# Schematic.net
KiCad netlist of a schematic drawn in Altium Designer
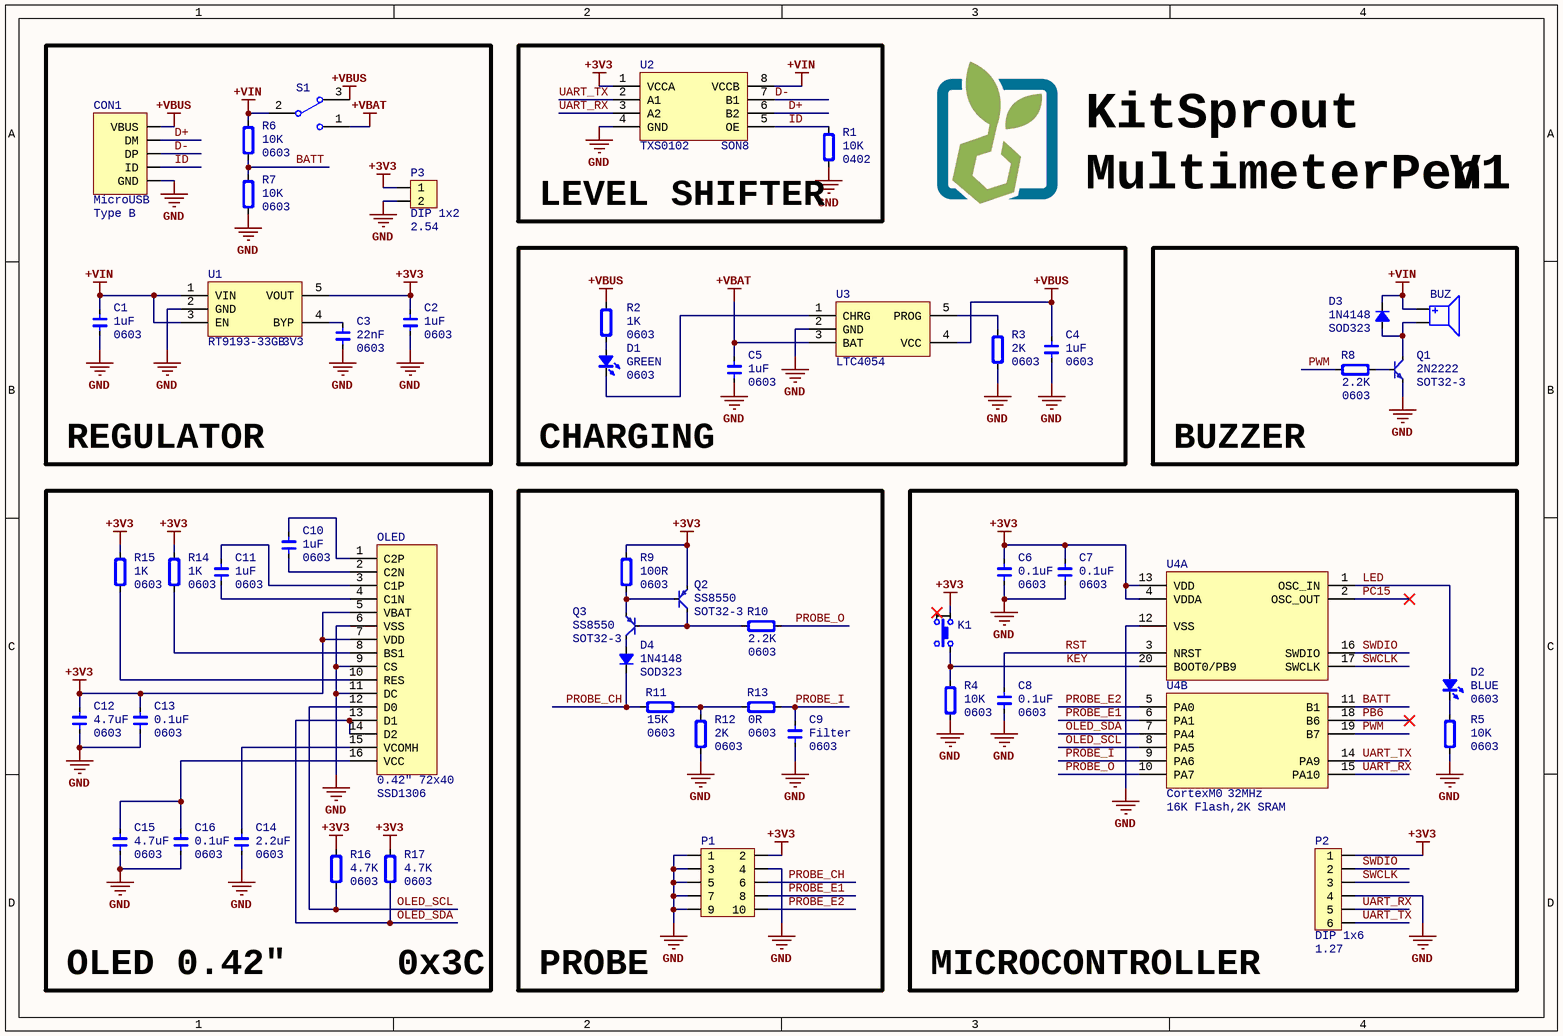
[diagram p0: Schematic.SchDoc]

(export (version "E")
  (design (tool "Eeschema 10.0.6"))
  (components
    (comp (ref "BUZ")
      (value "Buzzer")
      (footprint "PCB_Module:Buzzer_5x5")
      (libsource (lib "SCH_Module") (part "Buzzer"))
    )
    (comp (ref "C1")
      (value "1uF")
      (footprint "PCB_PassiveCap:CAP_0603")
      (description "Capacitor")
      (fields (field (name "TYPE") "0603") (field (name "Comment") "C0603"))
      (libsource (lib "SCH_Passive") (part "Cap_0603"))
    )
    (comp (ref "C2")
      (value "1uF")
      (footprint "PCB_PassiveCap:CAP_0603")
      (description "Capacitor")
      (fields (field (name "TYPE") "0603") (field (name "Comment") "C0603"))
      (libsource (lib "SCH_Passive") (part "Cap_0603"))
    )
    (comp (ref "C3")
      (value "22nF")
      (footprint "PCB_PassiveCap:CAP_0603")
      (description "Capacitor")
      (fields (field (name "TYPE") "0603") (field (name "Comment") "C0603"))
      (libsource (lib "SCH_Passive") (part "Cap_0603"))
    )
    (comp (ref "C4")
      (value "1uF")
      (footprint "PCB_PassiveCap:CAP_0603")
      (description "Capacitor")
      (fields (field (name "TYPE") "0603") (field (name "Comment") "C0603"))
      (libsource (lib "SCH_Passive") (part "Cap_0603"))
    )
    (comp (ref "C5")
      (value "1uF")
      (footprint "PCB_PassiveCap:CAP_0603")
      (description "Capacitor")
      (fields (field (name "TYPE") "0603") (field (name "Comment") "C0603"))
      (libsource (lib "SCH_Passive") (part "Cap_0603"))
    )
    (comp (ref "C6")
      (value "0.1uF")
      (footprint "PCB_PassiveCap:CAP_0603")
      (description "Capacitor")
      (fields (field (name "TYPE") "0603") (field (name "Comment") "C0603"))
      (libsource (lib "SCH_Passive") (part "Cap_0603"))
    )
    (comp (ref "C7")
      (value "0.1uF")
      (footprint "PCB_PassiveCap:CAP_0603")
      (description "Capacitor")
      (fields (field (name "TYPE") "0603") (field (name "Comment") "C0603"))
      (libsource (lib "SCH_Passive") (part "Cap_0603"))
    )
    (comp (ref "C8")
      (value "0.1uF")
      (footprint "PCB_PassiveCap:CAP_0603")
      (description "Capacitor")
      (fields (field (name "TYPE") "0603") (field (name "Comment") "C0603"))
      (libsource (lib "SCH_Passive") (part "Cap_0603"))
    )
    (comp (ref "C9")
      (value "Filter")
      (footprint "PCB_PassiveCap:CAP_0603")
      (description "Capacitor")
      (fields (field (name "TYPE") "0603") (field (name "Comment") "C0603"))
      (libsource (lib "SCH_Passive") (part "Cap_0603"))
    )
    (comp (ref "C10")
      (value "1uF")
      (footprint "PCB_PassiveCap:CAP_0603")
      (description "Capacitor")
      (fields (field (name "TYPE") "0603") (field (name "Comment") "C0603"))
      (libsource (lib "SCH_Passive") (part "Cap_0603"))
    )
    (comp (ref "C11")
      (value "1uF")
      (footprint "PCB_PassiveCap:CAP_0603")
      (description "Capacitor")
      (fields (field (name "TYPE") "0603") (field (name "Comment") "C0603"))
      (libsource (lib "SCH_Passive") (part "Cap_0603"))
    )
    (comp (ref "C12")
      (value "4.7uF")
      (footprint "PCB_PassiveCap:CAP_0603")
      (description "Capacitor")
      (fields (field (name "TYPE") "0603") (field (name "Comment") "C0603"))
      (libsource (lib "SCH_Passive") (part "Cap_0603"))
    )
    (comp (ref "C13")
      (value "0.1uF")
      (footprint "PCB_PassiveCap:CAP_0603")
      (description "Capacitor")
      (fields (field (name "TYPE") "0603") (field (name "Comment") "C0603"))
      (libsource (lib "SCH_Passive") (part "Cap_0603"))
    )
    (comp (ref "C14")
      (value "2.2uF")
      (footprint "PCB_PassiveCap:CAP_0603")
      (description "Capacitor")
      (fields (field (name "TYPE") "0603") (field (name "Comment") "C0603"))
      (libsource (lib "SCH_Passive") (part "Cap_0603"))
    )
    (comp (ref "C15")
      (value "4.7uF")
      (footprint "PCB_PassiveCap:CAP_0603")
      (description "Capacitor")
      (fields (field (name "TYPE") "0603") (field (name "Comment") "C0603"))
      (libsource (lib "SCH_Passive") (part "Cap_0603"))
    )
    (comp (ref "C16")
      (value "0.1uF")
      (footprint "PCB_PassiveCap:CAP_0603")
      (description "Capacitor")
      (fields (field (name "TYPE") "0603") (field (name "Comment") "C0603"))
      (libsource (lib "SCH_Passive") (part "Cap_0603"))
    )
    (comp (ref "CON1")
      (value "MicroUSB")
      (footprint "PCB_USB:USB_Micro-AB")
      (description "USB")
      (fields (field (name "ALTIUM_VALUE") "Type B"))
      (libsource (lib "SCH_USB") (part "USB_Micro"))
    )
    (comp (ref "D1")
      (value "GREEN")
      (footprint "PCB_ActiveLED:LED_0603_GREEN")
      (description "LED")
      (fields (field (name "TYPE") "0603") (field (name "Comment") "D0603"))
      (libsource (lib "SCH_Active") (part "LED_0603"))
    )
    (comp (ref "D2")
      (value "BLUE")
      (footprint "PCB_ActiveLED:LED_0603_BLUE")
      (description "LED")
      (fields (field (name "TYPE") "0603") (field (name "Comment") "D0603"))
      (libsource (lib "SCH_Active") (part "LED_0603"))
    )
    (comp (ref "D3")
      (value "1N4148")
      (footprint "PCB_ActiveDIO:SOD-323")
      (description "Diode")
      (fields (field (name "TYPE") "SOD323"))
      (libsource (lib "SCH_Active") (part "Diode_SOD323"))
    )
    (comp (ref "D4")
      (value "1N4148")
      (footprint "PCB_ActiveDIO:SOD-323")
      (description "Diode")
      (fields (field (name "TYPE") "SOD323"))
      (libsource (lib "SCH_Active") (part "Diode_SOD323"))
    )
    (comp (ref "K1")
      (value "TACT")
      (footprint "PCB_Switch:ButtonTACT_3.4*3.5_90")
      (description "Button")
      (libsource (lib "SCH_Switch") (part "ButtonTACT_90_3.4x3.5"))
    )
    (comp (ref "OLED")
      (value "0.42\" 72x40")
      (footprint "PCB_Module:OLED_0.42_72x40_SSD1306")
      (description "OLED")
      (fields (field (name "NOTE") "SSD1306") (field (name "Comment") "OLED_0.42_SSD1306"))
      (libsource (lib "SCH_Module") (part "OLED_0.42_SSD1306"))
    )
    (comp (ref "P1")
      (value "HDR2x5")
      (footprint "PCB_ConnectorHDR:HDR2X5_2.54_180HF")
      (description "Header")
      (libsource (lib "SCH_ConnectorHDR") (part "HDR2x5_2.54"))
    )
    (comp (ref "P2")
      (value "1.27")
      (footprint "PCB_ConnectorHDR:HDR1X6_1.27_180F")
      (description "Header")
      (fields (field (name "TYPE") "DIP 1x6") (field (name "Comment") "HDR1x6"))
      (libsource (lib "SCH_ConnectorHDR") (part "HDR1x6_1.27T"))
    )
    (comp (ref "P3")
      (value "2.54")
      (footprint "PCB_ConnectorHDR:HDR1X2_2.54_180H")
      (description "Header")
      (fields (field (name "TYPE") "DIP 1x2") (field (name "Comment") "HDR1x2"))
      (libsource (lib "SCH_ConnectorHDR") (part "HDR1x2_2.54"))
    )
    (comp (ref "Q1")
      (value "2N2222")
      (footprint "PCB_IntegratedCircuit:SOT23-3")
      (description "Transistor")
      (fields (field (name "TYPE") "SOT32-3"))
      (libsource (lib "SCH_Active") (part "BJT_NPN"))
    )
    (comp (ref "Q2")
      (value "SS8550")
      (footprint "PCB_IntegratedCircuit:SOT23-3")
      (description "Transistor")
      (fields (field (name "TYPE") "SOT32-3"))
      (libsource (lib "SCH_Active") (part "BJT_PNP"))
    )
    (comp (ref "Q3")
      (value "SS8550")
      (footprint "PCB_IntegratedCircuit:SOT23-3")
      (description "Transistor")
      (fields (field (name "TYPE") "SOT32-3"))
      (libsource (lib "SCH_Active") (part "BJT_PNP_T"))
    )
    (comp (ref "R1")
      (value "10K")
      (footprint "PCB_PassiveRes:RES_0402")
      (description "Resistor")
      (fields (field (name "TYPE") "0402") (field (name "Comment") "R0402"))
      (libsource (lib "SCH_Passive") (part "Res_0402"))
    )
    (comp (ref "R2")
      (value "1K")
      (footprint "PCB_PassiveRes:RES_0603")
      (description "Resistor")
      (fields (field (name "TYPE") "0603") (field (name "Comment") "R0603"))
      (libsource (lib "SCH_Passive") (part "Res_0603"))
    )
    (comp (ref "R3")
      (value "2K")
      (footprint "PCB_PassiveRes:RES_0603")
      (description "Resistor")
      (fields (field (name "TYPE") "0603") (field (name "Comment") "R0603"))
      (libsource (lib "SCH_Passive") (part "Res_0603"))
    )
    (comp (ref "R4")
      (value "10K")
      (footprint "PCB_PassiveRes:RES_0603")
      (description "Resistor")
      (fields (field (name "TYPE") "0603") (field (name "Comment") "R0603"))
      (libsource (lib "SCH_Passive") (part "Res_0603"))
    )
    (comp (ref "R5")
      (value "10K")
      (footprint "PCB_PassiveRes:RES_0603")
      (description "Resistor")
      (fields (field (name "TYPE") "0603") (field (name "Comment") "R0603"))
      (libsource (lib "SCH_Passive") (part "Res_0603"))
    )
    (comp (ref "R6")
      (value "10K")
      (footprint "PCB_PassiveRes:RES_0603")
      (description "Resistor")
      (fields (field (name "TYPE") "0603") (field (name "Comment") "R0603"))
      (libsource (lib "SCH_Passive") (part "Res_0603"))
    )
    (comp (ref "R7")
      (value "10K")
      (footprint "PCB_PassiveRes:RES_0603")
      (description "Resistor")
      (fields (field (name "TYPE") "0603") (field (name "Comment") "R0603"))
      (libsource (lib "SCH_Passive") (part "Res_0603"))
    )
    (comp (ref "R8")
      (value "2.2K")
      (footprint "PCB_PassiveRes:RES_0603")
      (description "Resistor")
      (fields (field (name "TYPE") "0603") (field (name "Comment") "R0603"))
      (libsource (lib "SCH_Passive") (part "Res_0603"))
    )
    (comp (ref "R9")
      (value "100R")
      (footprint "PCB_PassiveRes:RES_0603")
      (description "Resistor")
      (fields (field (name "TYPE") "0603") (field (name "Comment") "R0603"))
      (libsource (lib "SCH_Passive") (part "Res_0603"))
    )
    (comp (ref "R10")
      (value "2.2K")
      (footprint "PCB_PassiveRes:RES_0603")
      (description "Resistor")
      (fields (field (name "TYPE") "0603") (field (name "Comment") "R0603"))
      (libsource (lib "SCH_Passive") (part "Res_0603"))
    )
    (comp (ref "R11")
      (value "15K")
      (footprint "PCB_PassiveRes:RES_0603")
      (description "Resistor")
      (fields (field (name "TYPE") "0603") (field (name "Comment") "R0603"))
      (libsource (lib "SCH_Passive") (part "Res_0603"))
    )
    (comp (ref "R12")
      (value "2K")
      (footprint "PCB_PassiveRes:RES_0603")
      (description "Resistor")
      (fields (field (name "TYPE") "0603") (field (name "Comment") "R0603"))
      (libsource (lib "SCH_Passive") (part "Res_0603"))
    )
    (comp (ref "R13")
      (value "0R")
      (footprint "PCB_PassiveRes:RES_0603")
      (description "Resistor")
      (fields (field (name "TYPE") "0603") (field (name "Comment") "R0603"))
      (libsource (lib "SCH_Passive") (part "Res_0603"))
    )
    (comp (ref "R14")
      (value "1K")
      (footprint "PCB_PassiveRes:RES_0603")
      (description "Resistor")
      (fields (field (name "TYPE") "0603") (field (name "Comment") "R0603"))
      (libsource (lib "SCH_Passive") (part "Res_0603"))
    )
    (comp (ref "R15")
      (value "1K")
      (footprint "PCB_PassiveRes:RES_0603")
      (description "Resistor")
      (fields (field (name "TYPE") "0603") (field (name "Comment") "R0603"))
      (libsource (lib "SCH_Passive") (part "Res_0603"))
    )
    (comp (ref "R16")
      (value "4.7K")
      (footprint "PCB_PassiveRes:RES_0603")
      (description "Resistor")
      (fields (field (name "TYPE") "0603") (field (name "Comment") "R0603"))
      (libsource (lib "SCH_Passive") (part "Res_0603"))
    )
    (comp (ref "R17")
      (value "4.7K")
      (footprint "PCB_PassiveRes:RES_0603")
      (description "Resistor")
      (fields (field (name "TYPE") "0603") (field (name "Comment") "R0603"))
      (libsource (lib "SCH_Passive") (part "Res_0603"))
    )
    (comp (ref "S1")
      (value "SPDT")
      (footprint "PCB_Switch:SwitchSPDT_2.8X6.6_90")
      (description "Switch")
      (libsource (lib "SCH_Switch") (part "SwitchSPDT_90_2.8x6.6"))
    )
    (comp (ref "U1")
      (value "RT9193-33GB")
      (footprint "PCB_IntegratedCircuit:SOT23-5")
      (description "Power")
      (fields (field (name "ALTIUM_VALUE") "3V3"))
      (libsource (lib "SCH_Power") (part "RT9193"))
    )
    (comp (ref "U2")
      (value "TXS0102")
      (footprint "PCB_IntegratedCircuit:SON_P0.35_8")
      (description "Level Shifter")
      (fields (field (name "TYPE") "SON8") (field (name "MANUFACTURER") "Texas Instruments"))
      (libsource (lib "SCH_IntegratedCircuit") (part "TXS0102"))
    )
    (comp (ref "U3")
      (value "LTC4054")
      (footprint "PCB_IntegratedCircuit:SOT23-5")
      (description "Battery Charger")
      (libsource (lib "SCH_Power") (part "LTC4054"))
    )
    (comp (ref "U4")
      (value "STM32L011F4U6")
      (footprint "PCB_IntegratedCircuit:QFN_P0.5_20")
      (description "MCU ST")
      (fields
        (field (name "MANUFACTURER") "STMicroelectronics")
        (field (name "NOTE") "CortexM0")
        (field (name "SPECIFICATION") "16K Flash,2K SRAM")
        (field (name "Comment") "STM32L011F4U6")
      )
      (libsource (lib "SCH_Microcontroller") (part "STM32L011F"))
    )
  )
  (nets
    (net (code "1") (name "+3V3") (class "Default")
      (node (ref "C12") (pin "2") (pinfunction "2_2") (pintype "passive"))
      (node (ref "C13") (pin "2") (pinfunction "2_2") (pintype "passive"))
      (node (ref "C2") (pin "2") (pinfunction "2_2") (pintype "passive"))
      (node (ref "C6") (pin "2") (pinfunction "2_2") (pintype "passive"))
      (node (ref "C7") (pin "2") (pinfunction "2_2") (pintype "passive"))
      (node (ref "K1") (pin "1") (pinfunction "1_1") (pintype "passive"))
      (node (ref "OLED") (pin "5") (pinfunction "VBAT_5") (pintype "passive"))
      (node (ref "OLED") (pin "7") (pinfunction "VDD_7") (pintype "passive"))
      (node (ref "P1") (pin "2") (pinfunction "2_2") (pintype "passive"))
      (node (ref "P2") (pin "1") (pinfunction "1_1") (pintype "passive"))
      (node (ref "P3") (pin "1") (pinfunction "1_1") (pintype "passive"))
      (node (ref "Q2") (pin "2") (pinfunction "E_2") (pintype "passive"))
      (node (ref "R14") (pin "2") (pinfunction "2_2") (pintype "passive"))
      (node (ref "R15") (pin "2") (pinfunction "2_2") (pintype "passive"))
      (node (ref "R16") (pin "2") (pinfunction "2_2") (pintype "passive"))
      (node (ref "R17") (pin "2") (pinfunction "2_2") (pintype "passive"))
      (node (ref "R9") (pin "2") (pinfunction "2_2") (pintype "passive"))
      (node (ref "U1") (pin "5") (pinfunction "VOUT_5") (pintype "passive"))
      (node (ref "U2") (pin "1") (pinfunction "VCCA_1") (pintype "passive"))
      (node (ref "U4") (pin "13") (pinfunction "VDD_13") (pintype "passive"))
      (node (ref "U4") (pin "4") (pinfunction "VDDA_4") (pintype "passive"))
    )
    (net (code "2") (name "+VBAT") (class "Default")
      (node (ref "C5") (pin "2") (pinfunction "2_2") (pintype "passive"))
      (node (ref "S1") (pin "1") (pinfunction "1_1") (pintype "passive"))
      (node (ref "U3") (pin "3") (pinfunction "BAT_3") (pintype "passive"))
    )
    (net (code "3") (name "+VBUS") (class "Default")
      (node (ref "C4") (pin "2") (pinfunction "2_2") (pintype "passive"))
      (node (ref "CON1") (pin "1") (pinfunction "VBUS_1") (pintype "passive"))
      (node (ref "R2") (pin "2") (pinfunction "2_2") (pintype "passive"))
      (node (ref "S1") (pin "3") (pinfunction "3_3") (pintype "passive"))
      (node (ref "U3") (pin "4") (pinfunction "VCC_4") (pintype "passive"))
    )
    (net (code "4") (name "+VIN") (class "Default")
      (node (ref "BUZ") (pin "P") (pinfunction "Positive_P") (pintype "passive"))
      (node (ref "C1") (pin "2") (pinfunction "2_2") (pintype "passive"))
      (node (ref "D3") (pin "2") (pinfunction "K_2") (pintype "passive"))
      (node (ref "R6") (pin "2") (pinfunction "2_2") (pintype "passive"))
      (node (ref "S1") (pin "2") (pinfunction "2_2") (pintype "passive"))
      (node (ref "U1") (pin "1") (pinfunction "VIN_1") (pintype "passive"))
      (node (ref "U1") (pin "3") (pinfunction "EN_3") (pintype "power_in"))
      (node (ref "U2") (pin "8") (pinfunction "VCCB_8") (pintype "passive"))
    )
    (net (code "5") (name "/BATT") (class "Default")
      (node (ref "R6") (pin "1") (pinfunction "1_1") (pintype "passive"))
      (node (ref "R7") (pin "2") (pinfunction "2_2") (pintype "passive"))
      (node (ref "U4") (pin "11") (pinfunction "B1_11") (pintype "passive"))
    )
    (net (code "6") (name "/D+") (class "Default")
      (node (ref "CON1") (pin "2") (pinfunction "DM_2") (pintype "passive"))
      (node (ref "U2") (pin "6") (pinfunction "B2_6") (pintype "passive"))
    )
    (net (code "7") (name "/D-") (class "Default")
      (node (ref "CON1") (pin "3") (pinfunction "DP_3") (pintype "passive"))
      (node (ref "U2") (pin "7") (pinfunction "B1_7") (pintype "passive"))
    )
    (net (code "8") (name "/ID") (class "Default")
      (node (ref "CON1") (pin "4") (pinfunction "ID_4") (pintype "passive"))
      (node (ref "R1") (pin "2") (pinfunction "2_2") (pintype "passive"))
      (node (ref "U2") (pin "5") (pinfunction "OE_5") (pintype "passive"))
    )
    (net (code "9") (name "/KEY") (class "Default")
      (node (ref "K1") (pin "2") (pinfunction "2_2") (pintype "passive"))
      (node (ref "R4") (pin "2") (pinfunction "2_2") (pintype "passive"))
      (node (ref "U4") (pin "20") (pinfunction "BOOT0/PB9_20") (pintype "passive"))
    )
    (net (code "10") (name "/LED") (class "Default")
      (node (ref "D2") (pin "1") (pinfunction "A_1") (pintype "passive"))
      (node (ref "U4") (pin "1") (pinfunction "OSC_IN_1") (pintype "passive"))
    )
    (net (code "11") (name "/OLED_SCL") (class "Default")
      (node (ref "OLED") (pin "12") (pinfunction "D0_12") (pintype "passive"))
      (node (ref "R16") (pin "1") (pinfunction "1_1") (pintype "passive"))
      (node (ref "U4") (pin "8") (pinfunction "PA5_8") (pintype "passive"))
    )
    (net (code "12") (name "/OLED_SDA") (class "Default")
      (node (ref "OLED") (pin "13") (pinfunction "D1_13") (pintype "passive"))
      (node (ref "OLED") (pin "14") (pinfunction "D2_14") (pintype "passive"))
      (node (ref "R17") (pin "1") (pinfunction "1_1") (pintype "passive"))
      (node (ref "U4") (pin "7") (pinfunction "PA4_7") (pintype "passive"))
    )
    (net (code "13") (name "/PB6") (class "Default")
      (node (ref "U4") (pin "18") (pinfunction "B6_18") (pintype "passive+no_connect"))
    )
    (net (code "14") (name "/PC15") (class "Default")
      (node (ref "U4") (pin "2") (pinfunction "OSC_OUT_2") (pintype "passive+no_connect"))
    )
    (net (code "15") (name "/PROBE_CH") (class "Default")
      (node (ref "D4") (pin "2") (pinfunction "K_2") (pintype "passive"))
      (node (ref "P1") (pin "6") (pinfunction "6_6") (pintype "passive"))
      (node (ref "R11") (pin "2") (pinfunction "2_2") (pintype "passive"))
    )
    (net (code "16") (name "/PROBE_E1") (class "Default")
      (node (ref "P1") (pin "8") (pinfunction "8_8") (pintype "passive"))
      (node (ref "U4") (pin "6") (pinfunction "PA1_6") (pintype "passive"))
    )
    (net (code "17") (name "/PROBE_E2") (class "Default")
      (node (ref "P1") (pin "10") (pinfunction "10_10") (pintype "passive"))
      (node (ref "U4") (pin "5") (pinfunction "PA0_5") (pintype "passive"))
    )
    (net (code "18") (name "/PROBE_I") (class "Default")
      (node (ref "C9") (pin "2") (pinfunction "2_2") (pintype "passive"))
      (node (ref "R13") (pin "1") (pinfunction "1_1") (pintype "passive"))
      (node (ref "U4") (pin "9") (pinfunction "PA6_9") (pintype "passive"))
    )
    (net (code "19") (name "/PROBE_O") (class "Default")
      (node (ref "R10") (pin "1") (pinfunction "1_1") (pintype "passive"))
      (node (ref "U4") (pin "10") (pinfunction "PA7_10") (pintype "passive"))
    )
    (net (code "20") (name "/PWM") (class "Default")
      (node (ref "R8") (pin "2") (pinfunction "2_2") (pintype "passive"))
      (node (ref "U4") (pin "19") (pinfunction "B7_19") (pintype "passive"))
    )
    (net (code "21") (name "/RST") (class "Default")
      (node (ref "C8") (pin "2") (pinfunction "2_2") (pintype "passive"))
      (node (ref "U4") (pin "3") (pinfunction "NRST_3") (pintype "passive"))
    )
    (net (code "22") (name "/SWCLK") (class "Default")
      (node (ref "P2") (pin "3") (pinfunction "3_3") (pintype "passive"))
      (node (ref "U4") (pin "17") (pinfunction "SWCLK_17") (pintype "passive"))
    )
    (net (code "23") (name "/SWDIO") (class "Default")
      (node (ref "P2") (pin "2") (pinfunction "2_2") (pintype "passive"))
      (node (ref "U4") (pin "16") (pinfunction "SWDIO_16") (pintype "passive"))
    )
    (net (code "24") (name "/UART_RX") (class "Default")
      (node (ref "P2") (pin "5") (pinfunction "5_5") (pintype "passive"))
      (node (ref "U2") (pin "3") (pinfunction "A2_3") (pintype "passive"))
      (node (ref "U4") (pin "15") (pinfunction "PA10_15") (pintype "passive"))
    )
    (net (code "25") (name "/UART_TX") (class "Default")
      (node (ref "P2") (pin "6") (pinfunction "6_6") (pintype "passive"))
      (node (ref "U2") (pin "2") (pinfunction "A1_2") (pintype "passive"))
      (node (ref "U4") (pin "14") (pinfunction "PA9_14") (pintype "passive"))
    )
    (net (code "26") (name "GND") (class "Default")
      (node (ref "C1") (pin "1") (pinfunction "1_1") (pintype "passive"))
      (node (ref "C12") (pin "1") (pinfunction "1_1") (pintype "passive"))
      (node (ref "C13") (pin "1") (pinfunction "1_1") (pintype "passive"))
      (node (ref "C14") (pin "1") (pinfunction "1_1") (pintype "passive"))
      (node (ref "C15") (pin "1") (pinfunction "1_1") (pintype "passive"))
      (node (ref "C16") (pin "1") (pinfunction "1_1") (pintype "passive"))
      (node (ref "C2") (pin "1") (pinfunction "1_1") (pintype "passive"))
      (node (ref "C3") (pin "1") (pinfunction "1_1") (pintype "passive"))
      (node (ref "C4") (pin "1") (pinfunction "1_1") (pintype "passive"))
      (node (ref "C5") (pin "1") (pinfunction "1_1") (pintype "passive"))
      (node (ref "C6") (pin "1") (pinfunction "1_1") (pintype "passive"))
      (node (ref "C7") (pin "1") (pinfunction "1_1") (pintype "passive"))
      (node (ref "C8") (pin "1") (pinfunction "1_1") (pintype "passive"))
      (node (ref "C9") (pin "1") (pinfunction "1_1") (pintype "passive"))
      (node (ref "CON1") (pin "5") (pinfunction "GND_5") (pintype "passive"))
      (node (ref "OLED") (pin "11") (pinfunction "DC_11") (pintype "passive"))
      (node (ref "OLED") (pin "6") (pinfunction "VSS_6") (pintype "passive"))
      (node (ref "OLED") (pin "9") (pinfunction "CS_9") (pintype "passive"))
      (node (ref "P1") (pin "1") (pinfunction "1_1") (pintype "passive"))
      (node (ref "P1") (pin "3") (pinfunction "3_3") (pintype "passive"))
      (node (ref "P1") (pin "4") (pinfunction "4_4") (pintype "passive"))
      (node (ref "P1") (pin "5") (pinfunction "5_5") (pintype "passive"))
      (node (ref "P1") (pin "7") (pinfunction "7_7") (pintype "passive"))
      (node (ref "P1") (pin "9") (pinfunction "9_9") (pintype "passive"))
      (node (ref "P2") (pin "4") (pinfunction "4_4") (pintype "passive"))
      (node (ref "P3") (pin "2") (pinfunction "2_2") (pintype "passive"))
      (node (ref "Q1") (pin "2") (pinfunction "E_2") (pintype "passive"))
      (node (ref "R1") (pin "1") (pinfunction "1_1") (pintype "passive"))
      (node (ref "R12") (pin "1") (pinfunction "1_1") (pintype "passive"))
      (node (ref "R3") (pin "1") (pinfunction "1_1") (pintype "passive"))
      (node (ref "R4") (pin "1") (pinfunction "1_1") (pintype "passive"))
      (node (ref "R5") (pin "1") (pinfunction "1_1") (pintype "passive"))
      (node (ref "R7") (pin "1") (pinfunction "1_1") (pintype "passive"))
      (node (ref "U1") (pin "2") (pinfunction "GND_2") (pintype "passive"))
      (node (ref "U2") (pin "4") (pinfunction "GND_4") (pintype "passive"))
      (node (ref "U3") (pin "2") (pinfunction "GND_2") (pintype "passive"))
      (node (ref "U4") (pin "12") (pinfunction "VSS_12") (pintype "passive"))
    )
    (net (code "27") (name "Net-(BUZ-Negative)") (class "Default")
      (node (ref "BUZ") (pin "N") (pinfunction "Negative_N") (pintype "passive"))
      (node (ref "D3") (pin "1") (pinfunction "A_1") (pintype "passive"))
      (node (ref "Q1") (pin "3") (pinfunction "C_3") (pintype "passive"))
    )
    (net (code "28") (name "Net-(D1-A)") (class "Default")
      (node (ref "D1") (pin "1") (pinfunction "A_1") (pintype "passive"))
      (node (ref "R2") (pin "1") (pinfunction "1_1") (pintype "passive"))
    )
    (net (code "29") (name "Net-(D1-K)") (class "Default")
      (node (ref "D1") (pin "2") (pinfunction "K_2") (pintype "passive"))
      (node (ref "U3") (pin "1") (pinfunction "CHRG_1") (pintype "passive"))
    )
    (net (code "30") (name "Net-(D2-K)") (class "Default")
      (node (ref "D2") (pin "2") (pinfunction "K_2") (pintype "passive"))
      (node (ref "R5") (pin "2") (pinfunction "2_2") (pintype "passive"))
    )
    (net (code "31") (name "Net-(D4-A)") (class "Default")
      (node (ref "D4") (pin "1") (pinfunction "A_1") (pintype "passive"))
      (node (ref "Q3") (pin "3") (pinfunction "C_3") (pintype "passive"))
    )
    (net (code "32") (name "Net-(OLED-BS1)") (class "Default")
      (node (ref "OLED") (pin "8") (pinfunction "BS1_8") (pintype "passive"))
      (node (ref "R14") (pin "1") (pinfunction "1_1") (pintype "passive"))
    )
    (net (code "33") (name "Net-(OLED-C1N)") (class "Default")
      (node (ref "C11") (pin "1") (pinfunction "1_1") (pintype "passive"))
      (node (ref "OLED") (pin "4") (pinfunction "C1N_4") (pintype "passive"))
    )
    (net (code "34") (name "Net-(OLED-C1P)") (class "Default")
      (node (ref "C11") (pin "2") (pinfunction "2_2") (pintype "passive"))
      (node (ref "OLED") (pin "3") (pinfunction "C1P_3") (pintype "passive"))
    )
    (net (code "35") (name "Net-(OLED-C2N)") (class "Default")
      (node (ref "C10") (pin "1") (pinfunction "1_1") (pintype "passive"))
      (node (ref "OLED") (pin "2") (pinfunction "C2N_2") (pintype "passive"))
    )
    (net (code "36") (name "Net-(OLED-C2P)") (class "Default")
      (node (ref "C10") (pin "2") (pinfunction "2_2") (pintype "passive"))
      (node (ref "OLED") (pin "1") (pinfunction "C2P_1") (pintype "passive"))
    )
    (net (code "37") (name "Net-(OLED-RES)") (class "Default")
      (node (ref "OLED") (pin "10") (pinfunction "RES_10") (pintype "passive"))
      (node (ref "R15") (pin "1") (pinfunction "1_1") (pintype "passive"))
    )
    (net (code "38") (name "Net-(OLED-VCC)") (class "Default")
      (node (ref "C15") (pin "2") (pinfunction "2_2") (pintype "passive"))
      (node (ref "C16") (pin "2") (pinfunction "2_2") (pintype "passive"))
      (node (ref "OLED") (pin "16") (pinfunction "VCC_16") (pintype "passive"))
    )
    (net (code "39") (name "Net-(OLED-VCOMH)") (class "Default")
      (node (ref "C14") (pin "2") (pinfunction "2_2") (pintype "passive"))
      (node (ref "OLED") (pin "15") (pinfunction "VCOMH_15") (pintype "passive"))
    )
    (net (code "40") (name "Net-(Q1-B)") (class "Default")
      (node (ref "Q1") (pin "1") (pinfunction "B_1") (pintype "passive"))
      (node (ref "R8") (pin "1") (pinfunction "1_1") (pintype "passive"))
    )
    (net (code "41") (name "Net-(Q2-B)") (class "Default")
      (node (ref "Q2") (pin "1") (pinfunction "B_1") (pintype "passive"))
      (node (ref "Q3") (pin "2") (pinfunction "E_2") (pintype "passive"))
      (node (ref "R9") (pin "1") (pinfunction "1_1") (pintype "passive"))
    )
    (net (code "42") (name "Net-(Q2-C)") (class "Default")
      (node (ref "Q2") (pin "3") (pinfunction "C_3") (pintype "passive"))
      (node (ref "Q3") (pin "1") (pinfunction "B_1") (pintype "passive"))
      (node (ref "R10") (pin "2") (pinfunction "2_2") (pintype "passive"))
    )
    (net (code "43") (name "Net-(R11-Pad1)") (class "Default")
      (node (ref "R11") (pin "1") (pinfunction "1_1") (pintype "passive"))
      (node (ref "R12") (pin "2") (pinfunction "2_2") (pintype "passive"))
      (node (ref "R13") (pin "2") (pinfunction "2_2") (pintype "passive"))
    )
    (net (code "44") (name "Net-(U1-BYP)") (class "Default")
      (node (ref "C3") (pin "2") (pinfunction "2_2") (pintype "passive"))
      (node (ref "U1") (pin "4") (pinfunction "BYP_4") (pintype "passive"))
    )
    (net (code "45") (name "Net-(U3-PROG)") (class "Default")
      (node (ref "R3") (pin "2") (pinfunction "2_2") (pintype "passive"))
      (node (ref "U3") (pin "5") (pinfunction "PROG_5") (pintype "passive"))
    )
    (net (code "46") (name "unconnected-(CON1-SH-Pad0)") (class "Default")
      (node (ref "CON1") (pin "0") (pinfunction "SH_0") (pintype "passive"))
    )
    (net (code "47") (name "unconnected-(K1-Pad3)") (class "Default")
      (node (ref "K1") (pin "3") (pinfunction "3_3") (pintype "passive+no_connect"))
    )
  )
)
